# leds.net
KiCad netlist of a schematic drawn in Altium Designer
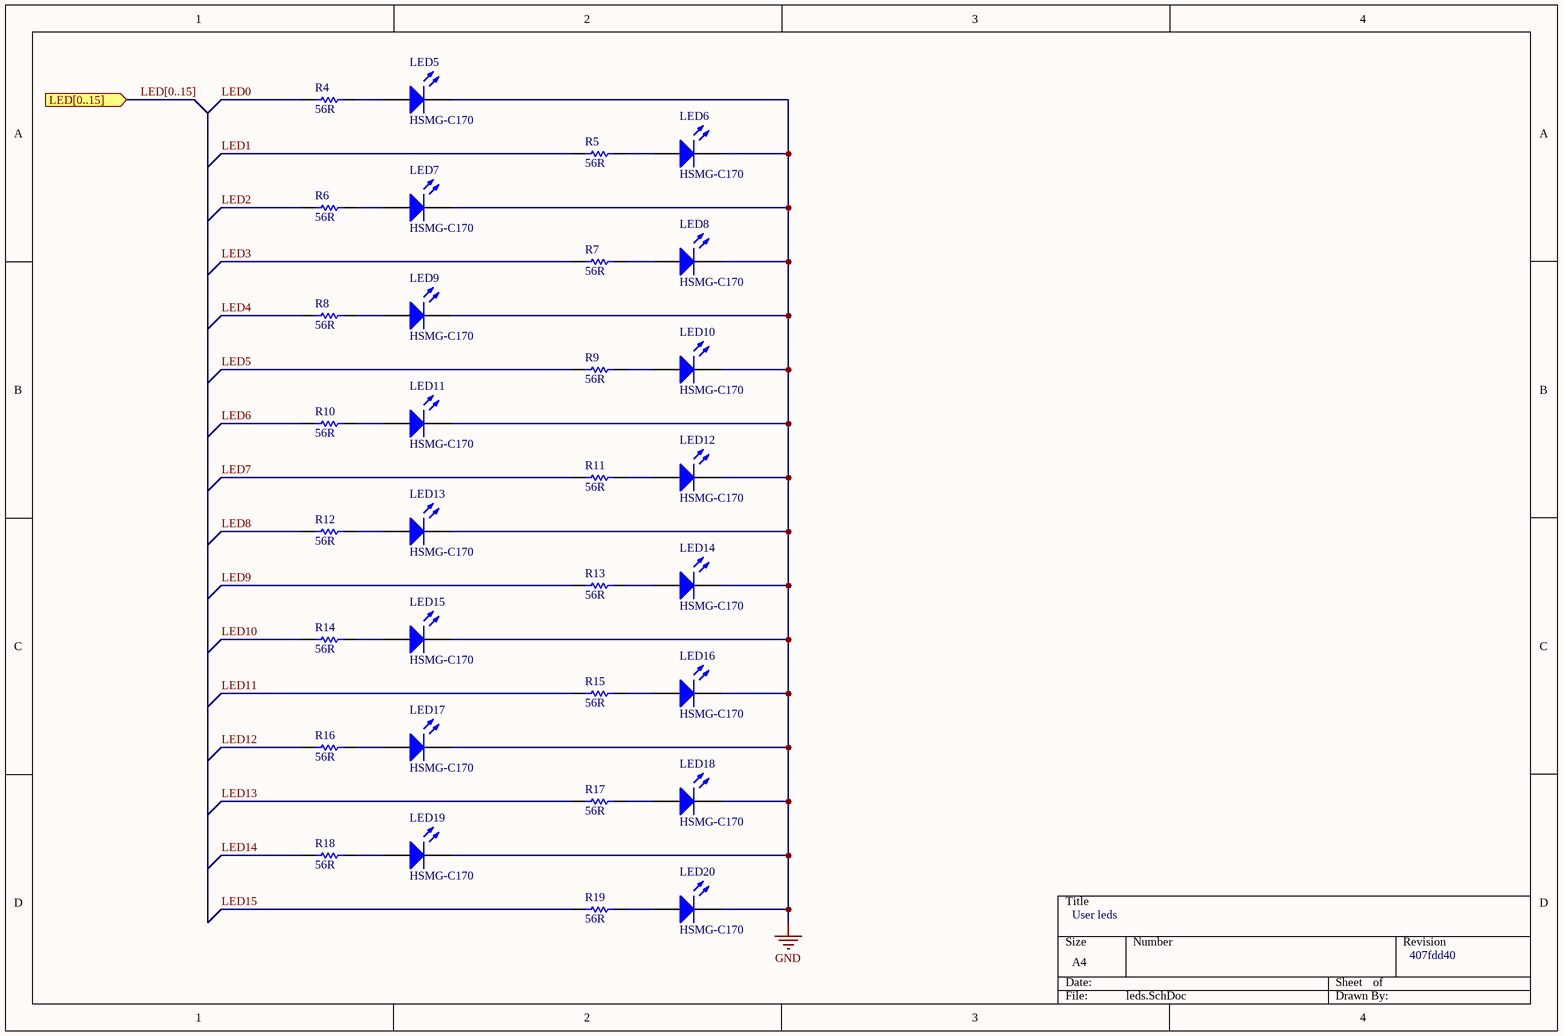
[diagram p0: leds.SchDoc]

(export (version "E")
  (design (tool "Eeschema 10.0.6"))
  (components
    (comp (ref "LED5")
      (value "HSMG-C170")
      (footprint "2.0X1.25X0.8")
      (description "Surface Mount Chip LED, Green")
      (fields (field (name "PUBLISHER") "Altium Limited"))
      (libsource (lib "Avago Optoelectronic LED") (part "HSMG-C170"))
    )
    (comp (ref "LED6")
      (value "HSMG-C170")
      (footprint "2.0X1.25X0.8")
      (description "Surface Mount Chip LED, Green")
      (fields (field (name "PUBLISHER") "Altium Limited"))
      (libsource (lib "Avago Optoelectronic LED") (part "HSMG-C170"))
    )
    (comp (ref "LED7")
      (value "HSMG-C170")
      (footprint "2.0X1.25X0.8")
      (description "Surface Mount Chip LED, Green")
      (fields (field (name "PUBLISHER") "Altium Limited"))
      (libsource (lib "Avago Optoelectronic LED") (part "HSMG-C170"))
    )
    (comp (ref "LED8")
      (value "HSMG-C170")
      (footprint "2.0X1.25X0.8")
      (description "Surface Mount Chip LED, Green")
      (fields (field (name "PUBLISHER") "Altium Limited"))
      (libsource (lib "Avago Optoelectronic LED") (part "HSMG-C170"))
    )
    (comp (ref "LED9")
      (value "HSMG-C170")
      (footprint "2.0X1.25X0.8")
      (description "Surface Mount Chip LED, Green")
      (fields (field (name "PUBLISHER") "Altium Limited"))
      (libsource (lib "Avago Optoelectronic LED") (part "HSMG-C170"))
    )
    (comp (ref "LED10")
      (value "HSMG-C170")
      (footprint "2.0X1.25X0.8")
      (description "Surface Mount Chip LED, Green")
      (fields (field (name "PUBLISHER") "Altium Limited"))
      (libsource (lib "Avago Optoelectronic LED") (part "HSMG-C170"))
    )
    (comp (ref "LED11")
      (value "HSMG-C170")
      (footprint "2.0X1.25X0.8")
      (description "Surface Mount Chip LED, Green")
      (fields (field (name "PUBLISHER") "Altium Limited"))
      (libsource (lib "Avago Optoelectronic LED") (part "HSMG-C170"))
    )
    (comp (ref "LED12")
      (value "HSMG-C170")
      (footprint "2.0X1.25X0.8")
      (description "Surface Mount Chip LED, Green")
      (fields (field (name "PUBLISHER") "Altium Limited"))
      (libsource (lib "Avago Optoelectronic LED") (part "HSMG-C170"))
    )
    (comp (ref "LED13")
      (value "HSMG-C170")
      (footprint "2.0X1.25X0.8")
      (description "Surface Mount Chip LED, Green")
      (fields (field (name "PUBLISHER") "Altium Limited"))
      (libsource (lib "Avago Optoelectronic LED") (part "HSMG-C170"))
    )
    (comp (ref "LED14")
      (value "HSMG-C170")
      (footprint "2.0X1.25X0.8")
      (description "Surface Mount Chip LED, Green")
      (fields (field (name "PUBLISHER") "Altium Limited"))
      (libsource (lib "Avago Optoelectronic LED") (part "HSMG-C170"))
    )
    (comp (ref "LED15")
      (value "HSMG-C170")
      (footprint "2.0X1.25X0.8")
      (description "Surface Mount Chip LED, Green")
      (fields (field (name "PUBLISHER") "Altium Limited"))
      (libsource (lib "Avago Optoelectronic LED") (part "HSMG-C170"))
    )
    (comp (ref "LED16")
      (value "HSMG-C170")
      (footprint "2.0X1.25X0.8")
      (description "Surface Mount Chip LED, Green")
      (fields (field (name "PUBLISHER") "Altium Limited"))
      (libsource (lib "Avago Optoelectronic LED") (part "HSMG-C170"))
    )
    (comp (ref "LED17")
      (value "HSMG-C170")
      (footprint "2.0X1.25X0.8")
      (description "Surface Mount Chip LED, Green")
      (fields (field (name "PUBLISHER") "Altium Limited"))
      (libsource (lib "Avago Optoelectronic LED") (part "HSMG-C170"))
    )
    (comp (ref "LED18")
      (value "HSMG-C170")
      (footprint "2.0X1.25X0.8")
      (description "Surface Mount Chip LED, Green")
      (fields (field (name "PUBLISHER") "Altium Limited"))
      (libsource (lib "Avago Optoelectronic LED") (part "HSMG-C170"))
    )
    (comp (ref "LED19")
      (value "HSMG-C170")
      (footprint "2.0X1.25X0.8")
      (description "Surface Mount Chip LED, Green")
      (fields (field (name "PUBLISHER") "Altium Limited"))
      (libsource (lib "Avago Optoelectronic LED") (part "HSMG-C170"))
    )
    (comp (ref "LED20")
      (value "HSMG-C170")
      (footprint "2.0X1.25X0.8")
      (description "Surface Mount Chip LED, Green")
      (fields (field (name "PUBLISHER") "Altium Limited"))
      (libsource (lib "Avago Optoelectronic LED") (part "HSMG-C170"))
    )
    (comp (ref "R4")
      (value "56R")
      (footprint "RESC1206(3216)_N")
      (description "56R 0.25W 5% 1206 (3216 Metric)  SMD")
      (fields (field (name "TOLERANCE") "5 %") (field (name "POWER") "0.25 W"))
      (libsource (lib "Altium Content Vault") (part "CMP-1014-00044-1"))
    )
    (comp (ref "R5")
      (value "56R")
      (footprint "RESC1206(3216)_N")
      (description "56R 0.25W 5% 1206 (3216 Metric)  SMD")
      (fields (field (name "TOLERANCE") "5 %") (field (name "POWER") "0.25 W"))
      (libsource (lib "Altium Content Vault") (part "CMP-1014-00044-1"))
    )
    (comp (ref "R6")
      (value "56R")
      (footprint "RESC1206(3216)_N")
      (description "56R 0.25W 5% 1206 (3216 Metric)  SMD")
      (fields (field (name "TOLERANCE") "5 %") (field (name "POWER") "0.25 W"))
      (libsource (lib "Altium Content Vault") (part "CMP-1014-00044-1"))
    )
    (comp (ref "R7")
      (value "56R")
      (footprint "RESC1206(3216)_N")
      (description "56R 0.25W 5% 1206 (3216 Metric)  SMD")
      (fields (field (name "TOLERANCE") "5 %") (field (name "POWER") "0.25 W"))
      (libsource (lib "Altium Content Vault") (part "CMP-1014-00044-1"))
    )
    (comp (ref "R8")
      (value "56R")
      (footprint "RESC1206(3216)_N")
      (description "56R 0.25W 5% 1206 (3216 Metric)  SMD")
      (fields (field (name "TOLERANCE") "5 %") (field (name "POWER") "0.25 W"))
      (libsource (lib "Altium Content Vault") (part "CMP-1014-00044-1"))
    )
    (comp (ref "R9")
      (value "56R")
      (footprint "RESC1206(3216)_N")
      (description "56R 0.25W 5% 1206 (3216 Metric)  SMD")
      (fields (field (name "TOLERANCE") "5 %") (field (name "POWER") "0.25 W"))
      (libsource (lib "Altium Content Vault") (part "CMP-1014-00044-1"))
    )
    (comp (ref "R10")
      (value "56R")
      (footprint "RESC1206(3216)_N")
      (description "56R 0.25W 5% 1206 (3216 Metric)  SMD")
      (fields (field (name "TOLERANCE") "5 %") (field (name "POWER") "0.25 W"))
      (libsource (lib "Altium Content Vault") (part "CMP-1014-00044-1"))
    )
    (comp (ref "R11")
      (value "56R")
      (footprint "RESC1206(3216)_N")
      (description "56R 0.25W 5% 1206 (3216 Metric)  SMD")
      (fields (field (name "TOLERANCE") "5 %") (field (name "POWER") "0.25 W"))
      (libsource (lib "Altium Content Vault") (part "CMP-1014-00044-1"))
    )
    (comp (ref "R12")
      (value "56R")
      (footprint "RESC1206(3216)_N")
      (description "56R 0.25W 5% 1206 (3216 Metric)  SMD")
      (fields (field (name "TOLERANCE") "5 %") (field (name "POWER") "0.25 W"))
      (libsource (lib "Altium Content Vault") (part "CMP-1014-00044-1"))
    )
    (comp (ref "R13")
      (value "56R")
      (footprint "RESC1206(3216)_N")
      (description "56R 0.25W 5% 1206 (3216 Metric)  SMD")
      (fields (field (name "TOLERANCE") "5 %") (field (name "POWER") "0.25 W"))
      (libsource (lib "Altium Content Vault") (part "CMP-1014-00044-1"))
    )
    (comp (ref "R14")
      (value "56R")
      (footprint "RESC1206(3216)_N")
      (description "56R 0.25W 5% 1206 (3216 Metric)  SMD")
      (fields (field (name "TOLERANCE") "5 %") (field (name "POWER") "0.25 W"))
      (libsource (lib "Altium Content Vault") (part "CMP-1014-00044-1"))
    )
    (comp (ref "R15")
      (value "56R")
      (footprint "RESC1206(3216)_N")
      (description "56R 0.25W 5% 1206 (3216 Metric)  SMD")
      (fields (field (name "TOLERANCE") "5 %") (field (name "POWER") "0.25 W"))
      (libsource (lib "Altium Content Vault") (part "CMP-1014-00044-1"))
    )
    (comp (ref "R16")
      (value "56R")
      (footprint "RESC1206(3216)_N")
      (description "56R 0.25W 5% 1206 (3216 Metric)  SMD")
      (fields (field (name "TOLERANCE") "5 %") (field (name "POWER") "0.25 W"))
      (libsource (lib "Altium Content Vault") (part "CMP-1014-00044-1"))
    )
    (comp (ref "R17")
      (value "56R")
      (footprint "RESC1206(3216)_N")
      (description "56R 0.25W 5% 1206 (3216 Metric)  SMD")
      (fields (field (name "TOLERANCE") "5 %") (field (name "POWER") "0.25 W"))
      (libsource (lib "Altium Content Vault") (part "CMP-1014-00044-1"))
    )
    (comp (ref "R18")
      (value "56R")
      (footprint "RESC1206(3216)_N")
      (description "56R 0.25W 5% 1206 (3216 Metric)  SMD")
      (fields (field (name "TOLERANCE") "5 %") (field (name "POWER") "0.25 W"))
      (libsource (lib "Altium Content Vault") (part "CMP-1014-00044-1"))
    )
    (comp (ref "R19")
      (value "56R")
      (footprint "RESC1206(3216)_N")
      (description "56R 0.25W 5% 1206 (3216 Metric)  SMD")
      (fields (field (name "TOLERANCE") "5 %") (field (name "POWER") "0.25 W"))
      (libsource (lib "Altium Content Vault") (part "CMP-1014-00044-1"))
    )
  )
  (nets
    (net (code "1") (name "/LED0") (class "Default")
      (node (ref "R4") (pin "1") (pinfunction "1_1") (pintype "passive"))
    )
    (net (code "2") (name "/LED1") (class "Default")
      (node (ref "R5") (pin "1") (pinfunction "1_1") (pintype "passive"))
    )
    (net (code "3") (name "/LED2") (class "Default")
      (node (ref "R6") (pin "1") (pinfunction "1_1") (pintype "passive"))
    )
    (net (code "4") (name "/LED3") (class "Default")
      (node (ref "R7") (pin "1") (pinfunction "1_1") (pintype "passive"))
    )
    (net (code "5") (name "/LED4") (class "Default")
      (node (ref "R8") (pin "1") (pinfunction "1_1") (pintype "passive"))
    )
    (net (code "6") (name "/LED5") (class "Default")
      (node (ref "R9") (pin "1") (pinfunction "1_1") (pintype "passive"))
    )
    (net (code "7") (name "/LED6") (class "Default")
      (node (ref "R10") (pin "1") (pinfunction "1_1") (pintype "passive"))
    )
    (net (code "8") (name "/LED7") (class "Default")
      (node (ref "R11") (pin "1") (pinfunction "1_1") (pintype "passive"))
    )
    (net (code "9") (name "/LED8") (class "Default")
      (node (ref "R12") (pin "1") (pinfunction "1_1") (pintype "passive"))
    )
    (net (code "10") (name "/LED9") (class "Default")
      (node (ref "R13") (pin "1") (pinfunction "1_1") (pintype "passive"))
    )
    (net (code "11") (name "/LED10") (class "Default")
      (node (ref "R14") (pin "1") (pinfunction "1_1") (pintype "passive"))
    )
    (net (code "12") (name "/LED11") (class "Default")
      (node (ref "R15") (pin "1") (pinfunction "1_1") (pintype "passive"))
    )
    (net (code "13") (name "/LED12") (class "Default")
      (node (ref "R16") (pin "1") (pinfunction "1_1") (pintype "passive"))
    )
    (net (code "14") (name "/LED13") (class "Default")
      (node (ref "R17") (pin "1") (pinfunction "1_1") (pintype "passive"))
    )
    (net (code "15") (name "/LED14") (class "Default")
      (node (ref "R18") (pin "1") (pinfunction "1_1") (pintype "passive"))
    )
    (net (code "16") (name "/LED15") (class "Default")
      (node (ref "R19") (pin "1") (pinfunction "1_1") (pintype "passive"))
    )
    (net (code "18") (name "GND") (class "Default")
      (node (ref "LED10") (pin "2") (pinfunction "K_2") (pintype "passive"))
      (node (ref "LED11") (pin "2") (pinfunction "K_2") (pintype "passive"))
      (node (ref "LED12") (pin "2") (pinfunction "K_2") (pintype "passive"))
      (node (ref "LED13") (pin "2") (pinfunction "K_2") (pintype "passive"))
      (node (ref "LED14") (pin "2") (pinfunction "K_2") (pintype "passive"))
      (node (ref "LED15") (pin "2") (pinfunction "K_2") (pintype "passive"))
      (node (ref "LED16") (pin "2") (pinfunction "K_2") (pintype "passive"))
      (node (ref "LED17") (pin "2") (pinfunction "K_2") (pintype "passive"))
      (node (ref "LED18") (pin "2") (pinfunction "K_2") (pintype "passive"))
      (node (ref "LED19") (pin "2") (pinfunction "K_2") (pintype "passive"))
      (node (ref "LED20") (pin "2") (pinfunction "K_2") (pintype "passive"))
      (node (ref "LED5") (pin "2") (pinfunction "K_2") (pintype "passive"))
      (node (ref "LED6") (pin "2") (pinfunction "K_2") (pintype "passive"))
      (node (ref "LED7") (pin "2") (pinfunction "K_2") (pintype "passive"))
      (node (ref "LED8") (pin "2") (pinfunction "K_2") (pintype "passive"))
      (node (ref "LED9") (pin "2") (pinfunction "K_2") (pintype "passive"))
    )
    (net (code "19") (name "Net-(LED5-A)") (class "Default")
      (node (ref "LED5") (pin "1") (pinfunction "A_1") (pintype "passive"))
      (node (ref "R4") (pin "2") (pinfunction "2_2") (pintype "passive"))
    )
    (net (code "20") (name "Net-(LED6-A)") (class "Default")
      (node (ref "LED6") (pin "1") (pinfunction "A_1") (pintype "passive"))
      (node (ref "R5") (pin "2") (pinfunction "2_2") (pintype "passive"))
    )
    (net (code "21") (name "Net-(LED7-A)") (class "Default")
      (node (ref "LED7") (pin "1") (pinfunction "A_1") (pintype "passive"))
      (node (ref "R6") (pin "2") (pinfunction "2_2") (pintype "passive"))
    )
    (net (code "22") (name "Net-(LED8-A)") (class "Default")
      (node (ref "LED8") (pin "1") (pinfunction "A_1") (pintype "passive"))
      (node (ref "R7") (pin "2") (pinfunction "2_2") (pintype "passive"))
    )
    (net (code "23") (name "Net-(LED9-A)") (class "Default")
      (node (ref "LED9") (pin "1") (pinfunction "A_1") (pintype "passive"))
      (node (ref "R8") (pin "2") (pinfunction "2_2") (pintype "passive"))
    )
    (net (code "24") (name "Net-(LED10-A)") (class "Default")
      (node (ref "LED10") (pin "1") (pinfunction "A_1") (pintype "passive"))
      (node (ref "R9") (pin "2") (pinfunction "2_2") (pintype "passive"))
    )
    (net (code "25") (name "Net-(LED11-A)") (class "Default")
      (node (ref "LED11") (pin "1") (pinfunction "A_1") (pintype "passive"))
      (node (ref "R10") (pin "2") (pinfunction "2_2") (pintype "passive"))
    )
    (net (code "26") (name "Net-(LED12-A)") (class "Default")
      (node (ref "LED12") (pin "1") (pinfunction "A_1") (pintype "passive"))
      (node (ref "R11") (pin "2") (pinfunction "2_2") (pintype "passive"))
    )
    (net (code "27") (name "Net-(LED13-A)") (class "Default")
      (node (ref "LED13") (pin "1") (pinfunction "A_1") (pintype "passive"))
      (node (ref "R12") (pin "2") (pinfunction "2_2") (pintype "passive"))
    )
    (net (code "28") (name "Net-(LED14-A)") (class "Default")
      (node (ref "LED14") (pin "1") (pinfunction "A_1") (pintype "passive"))
      (node (ref "R13") (pin "2") (pinfunction "2_2") (pintype "passive"))
    )
    (net (code "29") (name "Net-(LED15-A)") (class "Default")
      (node (ref "LED15") (pin "1") (pinfunction "A_1") (pintype "passive"))
      (node (ref "R14") (pin "2") (pinfunction "2_2") (pintype "passive"))
    )
    (net (code "30") (name "Net-(LED16-A)") (class "Default")
      (node (ref "LED16") (pin "1") (pinfunction "A_1") (pintype "passive"))
      (node (ref "R15") (pin "2") (pinfunction "2_2") (pintype "passive"))
    )
    (net (code "31") (name "Net-(LED17-A)") (class "Default")
      (node (ref "LED17") (pin "1") (pinfunction "A_1") (pintype "passive"))
      (node (ref "R16") (pin "2") (pinfunction "2_2") (pintype "passive"))
    )
    (net (code "32") (name "Net-(LED18-A)") (class "Default")
      (node (ref "LED18") (pin "1") (pinfunction "A_1") (pintype "passive"))
      (node (ref "R17") (pin "2") (pinfunction "2_2") (pintype "passive"))
    )
    (net (code "33") (name "Net-(LED19-A)") (class "Default")
      (node (ref "LED19") (pin "1") (pinfunction "A_1") (pintype "passive"))
      (node (ref "R18") (pin "2") (pinfunction "2_2") (pintype "passive"))
    )
    (net (code "34") (name "Net-(LED20-A)") (class "Default")
      (node (ref "LED20") (pin "1") (pinfunction "A_1") (pintype "passive"))
      (node (ref "R19") (pin "2") (pinfunction "2_2") (pintype "passive"))
    )
  )
)
